# R181A.net
KiCad netlist of a schematic drawn in EAGLE
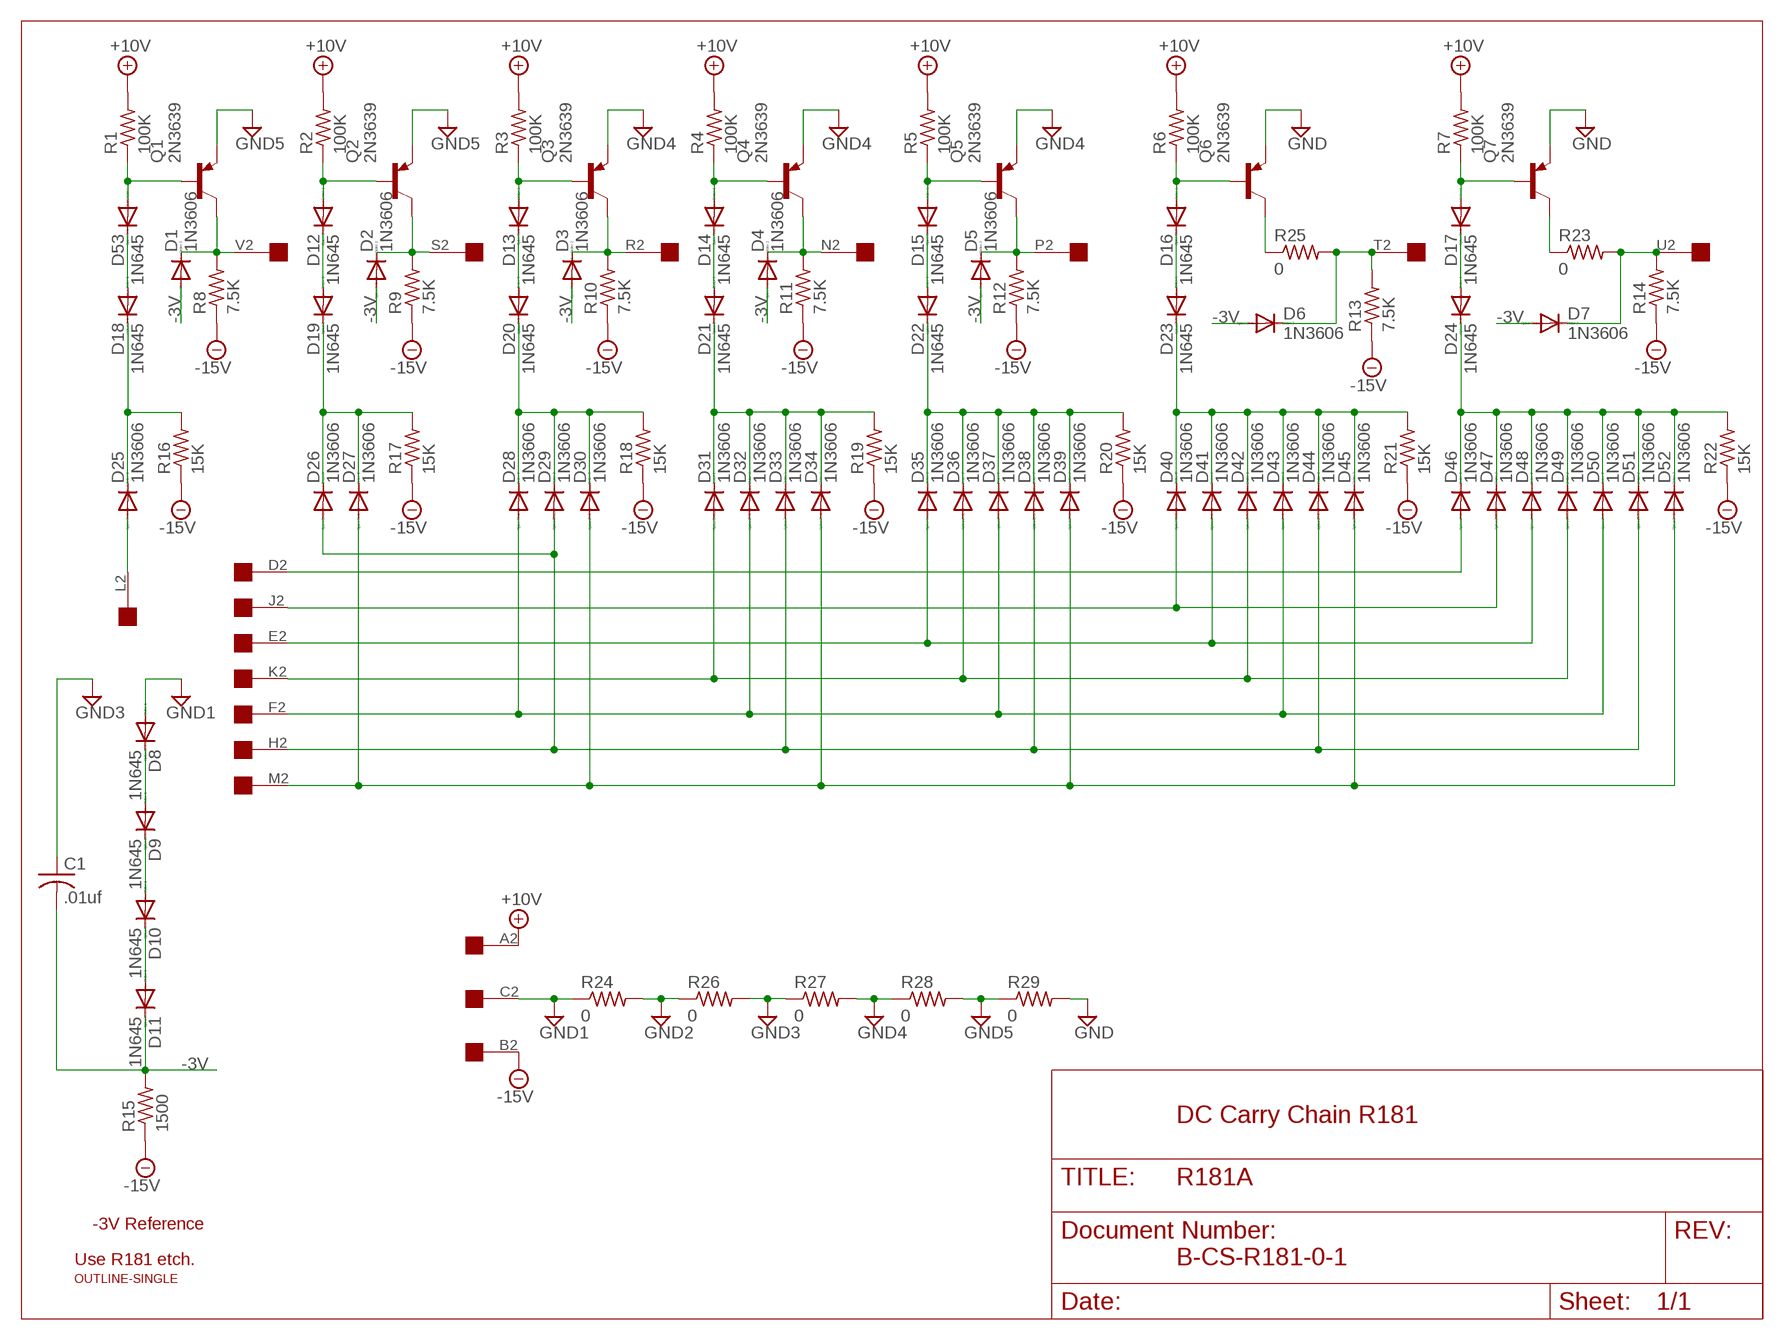
[diagram p0: schematic, sheet 1]

(export (version "E")
  (design (tool "Eeschema 10.0.6"))
  (components
    (comp (ref "C1")
      (value ".01uf")
      (footprint "eagle-import:C050-025X075")
      (libsource (lib "eagle-import") (part "C-US050-025X075"))
    )
    (comp (ref "D1")
      (value "1N3606")
      (footprint "eagle-import:DO35-10")
      (libsource (lib "eagle-import") (part "1N4148DO35-10"))
    )
    (comp (ref "D2")
      (value "1N3606")
      (footprint "eagle-import:DO35-10")
      (libsource (lib "eagle-import") (part "1N4148DO35-10"))
    )
    (comp (ref "D3")
      (value "1N3606")
      (footprint "eagle-import:DO35-10")
      (libsource (lib "eagle-import") (part "1N4148DO35-10"))
    )
    (comp (ref "D4")
      (value "1N3606")
      (footprint "eagle-import:DO35-10")
      (libsource (lib "eagle-import") (part "1N4148DO35-10"))
    )
    (comp (ref "D5")
      (value "1N3606")
      (footprint "eagle-import:DO35-10")
      (libsource (lib "eagle-import") (part "1N4148DO35-10"))
    )
    (comp (ref "D6")
      (value "1N3606")
      (footprint "eagle-import:DO35-10")
      (libsource (lib "eagle-import") (part "1N4148DO35-10"))
    )
    (comp (ref "D7")
      (value "1N3606")
      (footprint "eagle-import:DO35-10")
      (libsource (lib "eagle-import") (part "1N4148DO35-10"))
    )
    (comp (ref "D8")
      (value "1N645")
      (footprint "eagle-import:DO35-10")
      (libsource (lib "eagle-import") (part "1N4148DO35-10"))
    )
    (comp (ref "D9")
      (value "1N645")
      (footprint "eagle-import:DO35-10")
      (libsource (lib "eagle-import") (part "1N4148DO35-10"))
    )
    (comp (ref "D10")
      (value "1N645")
      (footprint "eagle-import:DO35-10")
      (libsource (lib "eagle-import") (part "1N4148DO35-10"))
    )
    (comp (ref "D11")
      (value "1N645")
      (footprint "eagle-import:DO35-10")
      (libsource (lib "eagle-import") (part "1N4148DO35-10"))
    )
    (comp (ref "D12")
      (value "1N645")
      (footprint "eagle-import:DO35-10")
      (libsource (lib "eagle-import") (part "1N4148DO35-10"))
    )
    (comp (ref "D13")
      (value "1N645")
      (footprint "eagle-import:DO35-10")
      (libsource (lib "eagle-import") (part "1N4148DO35-10"))
    )
    (comp (ref "D14")
      (value "1N645")
      (footprint "eagle-import:DO35-10")
      (libsource (lib "eagle-import") (part "1N4148DO35-10"))
    )
    (comp (ref "D15")
      (value "1N645")
      (footprint "eagle-import:DO35-10")
      (libsource (lib "eagle-import") (part "1N4148DO35-10"))
    )
    (comp (ref "D16")
      (value "1N645")
      (footprint "eagle-import:DO35-10")
      (libsource (lib "eagle-import") (part "1N4148DO35-10"))
    )
    (comp (ref "D17")
      (value "1N645")
      (footprint "eagle-import:DO35-10")
      (libsource (lib "eagle-import") (part "1N4148DO35-10"))
    )
    (comp (ref "D18")
      (value "1N645")
      (footprint "eagle-import:DO35-10")
      (libsource (lib "eagle-import") (part "1N4148DO35-10"))
    )
    (comp (ref "D19")
      (value "1N645")
      (footprint "eagle-import:DO35-10")
      (libsource (lib "eagle-import") (part "1N4148DO35-10"))
    )
    (comp (ref "D20")
      (value "1N645")
      (footprint "eagle-import:DO35-10")
      (libsource (lib "eagle-import") (part "1N4148DO35-10"))
    )
    (comp (ref "D21")
      (value "1N645")
      (footprint "eagle-import:DO35-10")
      (libsource (lib "eagle-import") (part "1N4148DO35-10"))
    )
    (comp (ref "D22")
      (value "1N645")
      (footprint "eagle-import:DO35-10")
      (libsource (lib "eagle-import") (part "1N4148DO35-10"))
    )
    (comp (ref "D23")
      (value "1N645")
      (footprint "eagle-import:DO35-10")
      (libsource (lib "eagle-import") (part "1N4148DO35-10"))
    )
    (comp (ref "D24")
      (value "1N645")
      (footprint "eagle-import:DO35-10")
      (libsource (lib "eagle-import") (part "1N4148DO35-10"))
    )
    (comp (ref "D25")
      (value "1N3606")
      (footprint "eagle-import:DO35-10")
      (libsource (lib "eagle-import") (part "1N4148DO35-10"))
    )
    (comp (ref "D26")
      (value "1N3606")
      (footprint "eagle-import:DO35-10")
      (libsource (lib "eagle-import") (part "1N4148DO35-10"))
    )
    (comp (ref "D27")
      (value "1N3606")
      (footprint "eagle-import:DO35-10")
      (libsource (lib "eagle-import") (part "1N4148DO35-10"))
    )
    (comp (ref "D28")
      (value "1N3606")
      (footprint "eagle-import:DO35-10")
      (libsource (lib "eagle-import") (part "1N4148DO35-10"))
    )
    (comp (ref "D29")
      (value "1N3606")
      (footprint "eagle-import:DO35-10")
      (libsource (lib "eagle-import") (part "1N4148DO35-10"))
    )
    (comp (ref "D30")
      (value "1N3606")
      (footprint "eagle-import:DO35-10")
      (libsource (lib "eagle-import") (part "1N4148DO35-10"))
    )
    (comp (ref "D31")
      (value "1N3606")
      (footprint "eagle-import:DO35-10")
      (libsource (lib "eagle-import") (part "1N4148DO35-10"))
    )
    (comp (ref "D32")
      (value "1N3606")
      (footprint "eagle-import:DO35-10")
      (libsource (lib "eagle-import") (part "1N4148DO35-10"))
    )
    (comp (ref "D33")
      (value "1N3606")
      (footprint "eagle-import:DO35-10")
      (libsource (lib "eagle-import") (part "1N4148DO35-10"))
    )
    (comp (ref "D34")
      (value "1N3606")
      (footprint "eagle-import:DO35-10")
      (libsource (lib "eagle-import") (part "1N4148DO35-10"))
    )
    (comp (ref "D35")
      (value "1N3606")
      (footprint "eagle-import:DO35-10")
      (libsource (lib "eagle-import") (part "1N4148DO35-10"))
    )
    (comp (ref "D36")
      (value "1N3606")
      (footprint "eagle-import:DO35-10")
      (libsource (lib "eagle-import") (part "1N4148DO35-10"))
    )
    (comp (ref "D37")
      (value "1N3606")
      (footprint "eagle-import:DO35-10")
      (libsource (lib "eagle-import") (part "1N4148DO35-10"))
    )
    (comp (ref "D38")
      (value "1N3606")
      (footprint "eagle-import:DO35-10")
      (libsource (lib "eagle-import") (part "1N4148DO35-10"))
    )
    (comp (ref "D39")
      (value "1N3606")
      (footprint "eagle-import:DO35-10")
      (libsource (lib "eagle-import") (part "1N4148DO35-10"))
    )
    (comp (ref "D40")
      (value "1N3606")
      (footprint "eagle-import:DO35-10")
      (libsource (lib "eagle-import") (part "1N4148DO35-10"))
    )
    (comp (ref "D41")
      (value "1N3606")
      (footprint "eagle-import:DO35-10")
      (libsource (lib "eagle-import") (part "1N4148DO35-10"))
    )
    (comp (ref "D42")
      (value "1N3606")
      (footprint "eagle-import:DO35-10")
      (libsource (lib "eagle-import") (part "1N4148DO35-10"))
    )
    (comp (ref "D43")
      (value "1N3606")
      (footprint "eagle-import:DO35-10")
      (libsource (lib "eagle-import") (part "1N4148DO35-10"))
    )
    (comp (ref "D44")
      (value "1N3606")
      (footprint "eagle-import:DO35-10")
      (libsource (lib "eagle-import") (part "1N4148DO35-10"))
    )
    (comp (ref "D45")
      (value "1N3606")
      (footprint "eagle-import:DO35-10")
      (libsource (lib "eagle-import") (part "1N4148DO35-10"))
    )
    (comp (ref "D46")
      (value "1N3606")
      (footprint "eagle-import:DO35-10")
      (libsource (lib "eagle-import") (part "1N4148DO35-10"))
    )
    (comp (ref "D47")
      (value "1N3606")
      (footprint "eagle-import:DO35-10")
      (libsource (lib "eagle-import") (part "1N4148DO35-10"))
    )
    (comp (ref "D48")
      (value "1N3606")
      (footprint "eagle-import:DO35-10")
      (libsource (lib "eagle-import") (part "1N4148DO35-10"))
    )
    (comp (ref "D49")
      (value "1N3606")
      (footprint "eagle-import:DO35-10")
      (libsource (lib "eagle-import") (part "1N4148DO35-10"))
    )
    (comp (ref "D50")
      (value "1N3606")
      (footprint "eagle-import:DO35-10")
      (libsource (lib "eagle-import") (part "1N4148DO35-10"))
    )
    (comp (ref "D51")
      (value "1N3606")
      (footprint "eagle-import:DO35-10")
      (libsource (lib "eagle-import") (part "1N4148DO35-10"))
    )
    (comp (ref "D52")
      (value "1N3606")
      (footprint "eagle-import:DO35-10")
      (libsource (lib "eagle-import") (part "1N4148DO35-10"))
    )
    (comp (ref "D53")
      (value "1N645")
      (footprint "eagle-import:DO35-10")
      (libsource (lib "eagle-import") (part "1N4148DO35-10"))
    )
    (comp (ref "Q1")
      (value "2N3639")
      (footprint "eagle-import:TO39")
      (libsource (lib "eagle-import") (part "2N3637"))
    )
    (comp (ref "Q2")
      (value "2N3639")
      (footprint "eagle-import:TO39")
      (libsource (lib "eagle-import") (part "2N3637"))
    )
    (comp (ref "Q3")
      (value "2N3639")
      (footprint "eagle-import:TO39")
      (libsource (lib "eagle-import") (part "2N3637"))
    )
    (comp (ref "Q4")
      (value "2N3639")
      (footprint "eagle-import:TO39")
      (libsource (lib "eagle-import") (part "2N3637"))
    )
    (comp (ref "Q5")
      (value "2N3639")
      (footprint "eagle-import:TO39")
      (libsource (lib "eagle-import") (part "2N3637"))
    )
    (comp (ref "Q6")
      (value "2N3639")
      (footprint "eagle-import:TO39")
      (libsource (lib "eagle-import") (part "2N3637"))
    )
    (comp (ref "Q7")
      (value "2N3639")
      (footprint "eagle-import:TO39")
      (libsource (lib "eagle-import") (part "2N3637"))
    )
    (comp (ref "R1")
      (value "100K")
      (footprint "eagle-import:0207_10")
      (libsource (lib "eagle-import") (part "R-US_0207/10"))
    )
    (comp (ref "R2")
      (value "100K")
      (footprint "eagle-import:0207_10")
      (libsource (lib "eagle-import") (part "R-US_0207/10"))
    )
    (comp (ref "R3")
      (value "100K")
      (footprint "eagle-import:0207_10")
      (libsource (lib "eagle-import") (part "R-US_0207/10"))
    )
    (comp (ref "R4")
      (value "100K")
      (footprint "eagle-import:0207_10")
      (libsource (lib "eagle-import") (part "R-US_0207/10"))
    )
    (comp (ref "R5")
      (value "100K")
      (footprint "eagle-import:0207_10")
      (libsource (lib "eagle-import") (part "R-US_0207/10"))
    )
    (comp (ref "R6")
      (value "100K")
      (footprint "eagle-import:0207_10")
      (libsource (lib "eagle-import") (part "R-US_0207/10"))
    )
    (comp (ref "R7")
      (value "100K")
      (footprint "eagle-import:0207_10")
      (libsource (lib "eagle-import") (part "R-US_0207/10"))
    )
    (comp (ref "R8")
      (value "7.5K")
      (footprint "eagle-import:0207_10")
      (libsource (lib "eagle-import") (part "R-US_0207/10"))
    )
    (comp (ref "R9")
      (value "7.5K")
      (footprint "eagle-import:0207_10")
      (libsource (lib "eagle-import") (part "R-US_0207/10"))
    )
    (comp (ref "R10")
      (value "7.5K")
      (footprint "eagle-import:0207_10")
      (libsource (lib "eagle-import") (part "R-US_0207/10"))
    )
    (comp (ref "R11")
      (value "7.5K")
      (footprint "eagle-import:0207_10")
      (libsource (lib "eagle-import") (part "R-US_0207/10"))
    )
    (comp (ref "R12")
      (value "7.5K")
      (footprint "eagle-import:0207_10")
      (libsource (lib "eagle-import") (part "R-US_0207/10"))
    )
    (comp (ref "R13")
      (value "7.5K")
      (footprint "eagle-import:0207_10")
      (libsource (lib "eagle-import") (part "R-US_0207/10"))
    )
    (comp (ref "R14")
      (value "7.5K")
      (footprint "eagle-import:0207_10")
      (libsource (lib "eagle-import") (part "R-US_0207/10"))
    )
    (comp (ref "R15")
      (value "1500")
      (footprint "eagle-import:0207_10")
      (libsource (lib "eagle-import") (part "R-US_0207/10"))
    )
    (comp (ref "R16")
      (value "15K")
      (footprint "eagle-import:0207_10")
      (libsource (lib "eagle-import") (part "R-US_0207/10"))
    )
    (comp (ref "R17")
      (value "15K")
      (footprint "eagle-import:0207_10")
      (libsource (lib "eagle-import") (part "R-US_0207/10"))
    )
    (comp (ref "R18")
      (value "15K")
      (footprint "eagle-import:0207_10")
      (libsource (lib "eagle-import") (part "R-US_0207/10"))
    )
    (comp (ref "R19")
      (value "15K")
      (footprint "eagle-import:0207_10")
      (libsource (lib "eagle-import") (part "R-US_0207/10"))
    )
    (comp (ref "R20")
      (value "15K")
      (footprint "eagle-import:0207_10")
      (libsource (lib "eagle-import") (part "R-US_0207/10"))
    )
    (comp (ref "R21")
      (value "15K")
      (footprint "eagle-import:0207_10")
      (libsource (lib "eagle-import") (part "R-US_0207/10"))
    )
    (comp (ref "R22")
      (value "15K")
      (footprint "eagle-import:0207_10")
      (libsource (lib "eagle-import") (part "R-US_0207/10"))
    )
    (comp (ref "R23")
      (value "0")
      (footprint "eagle-import:0207_10")
      (libsource (lib "eagle-import") (part "R-US_0207/10"))
    )
    (comp (ref "R24")
      (value "0")
      (footprint "eagle-import:0207_10")
      (libsource (lib "eagle-import") (part "R-US_0207/10"))
    )
    (comp (ref "R25")
      (value "0")
      (footprint "eagle-import:0207_10")
      (libsource (lib "eagle-import") (part "R-US_0207/10"))
    )
    (comp (ref "R26")
      (value "0")
      (footprint "eagle-import:0207_10")
      (libsource (lib "eagle-import") (part "R-US_0207/10"))
    )
    (comp (ref "R27")
      (value "0")
      (footprint "eagle-import:0207_10")
      (libsource (lib "eagle-import") (part "R-US_0207/10"))
    )
    (comp (ref "R28")
      (value "0")
      (footprint "eagle-import:0207_10")
      (libsource (lib "eagle-import") (part "R-US_0207/10"))
    )
    (comp (ref "R29")
      (value "0")
      (footprint "eagle-import:0207_10")
      (libsource (lib "eagle-import") (part "R-US_0207/10"))
    )
    (comp (ref "U$1")
      (value "OUTLINE-SINGLE")
      (footprint "eagle-import:SINGLE")
      (libsource (lib "eagle-import") (part "OUTLINE-SINGLE"))
    )
    (comp (ref "U$2")
      (value "EDGE-1")
      (footprint "eagle-import:EDGE-CON1")
      (libsource (lib "eagle-import") (part "EDGE-1"))
    )
  )
  (nets
    (net (code "1") (name "+10V") (class "Default")
      (node (ref "R1") (pin "2") (pinfunction "2_2") (pintype "passive"))
      (node (ref "R2") (pin "2") (pinfunction "2_2") (pintype "passive"))
      (node (ref "R3") (pin "2") (pinfunction "2_2") (pintype "passive"))
      (node (ref "R4") (pin "2") (pinfunction "2_2") (pintype "passive"))
      (node (ref "R5") (pin "2") (pinfunction "2_2") (pintype "passive"))
      (node (ref "R6") (pin "2") (pinfunction "2_2") (pintype "passive"))
      (node (ref "R7") (pin "2") (pinfunction "2_2") (pintype "passive"))
      (node (ref "U$2") (pin "A2") (pinfunction "1_A2") (pintype "bidirectional"))
    )
    (net (code "2") (name "-15V") (class "Default")
      (node (ref "R10") (pin "1") (pinfunction "1_1") (pintype "passive"))
      (node (ref "R11") (pin "1") (pinfunction "1_1") (pintype "passive"))
      (node (ref "R12") (pin "1") (pinfunction "1_1") (pintype "passive"))
      (node (ref "R13") (pin "1") (pinfunction "1_1") (pintype "passive"))
      (node (ref "R14") (pin "1") (pinfunction "1_1") (pintype "passive"))
      (node (ref "R15") (pin "1") (pinfunction "1_1") (pintype "passive"))
      (node (ref "R16") (pin "1") (pinfunction "1_1") (pintype "passive"))
      (node (ref "R17") (pin "1") (pinfunction "1_1") (pintype "passive"))
      (node (ref "R18") (pin "1") (pinfunction "1_1") (pintype "passive"))
      (node (ref "R19") (pin "1") (pinfunction "1_1") (pintype "passive"))
      (node (ref "R20") (pin "1") (pinfunction "1_1") (pintype "passive"))
      (node (ref "R21") (pin "1") (pinfunction "1_1") (pintype "passive"))
      (node (ref "R22") (pin "1") (pinfunction "1_1") (pintype "passive"))
      (node (ref "R8") (pin "1") (pinfunction "1_1") (pintype "passive"))
      (node (ref "R9") (pin "1") (pinfunction "1_1") (pintype "passive"))
      (node (ref "U$2") (pin "B2") (pinfunction "1_B2") (pintype "bidirectional"))
    )
    (net (code "3") (name "/-3V") (class "Default")
      (node (ref "C1") (pin "2") (pinfunction "2_2") (pintype "passive"))
      (node (ref "D1") (pin "A") (pinfunction "A_A") (pintype "passive"))
      (node (ref "D11") (pin "C") (pinfunction "C_C") (pintype "passive"))
      (node (ref "D2") (pin "A") (pinfunction "A_A") (pintype "passive"))
      (node (ref "D3") (pin "A") (pinfunction "A_A") (pintype "passive"))
      (node (ref "D4") (pin "A") (pinfunction "A_A") (pintype "passive"))
      (node (ref "D5") (pin "A") (pinfunction "A_A") (pintype "passive"))
      (node (ref "D6") (pin "A") (pinfunction "A_A") (pintype "passive"))
      (node (ref "D7") (pin "A") (pinfunction "A_A") (pintype "passive"))
      (node (ref "R15") (pin "2") (pinfunction "2_2") (pintype "passive"))
    )
    (net (code "4") (name "GND") (class "Default")
      (node (ref "Q6") (pin "1") (pinfunction "E_1") (pintype "passive"))
      (node (ref "Q7") (pin "1") (pinfunction "E_1") (pintype "passive"))
      (node (ref "R29") (pin "2") (pinfunction "2_2") (pintype "passive"))
    )
    (net (code "5") (name "GND1") (class "Default")
      (node (ref "D8") (pin "A") (pinfunction "A_A") (pintype "passive"))
      (node (ref "R24") (pin "1") (pinfunction "1_1") (pintype "passive"))
      (node (ref "U$2") (pin "C2") (pinfunction "1_C2") (pintype "bidirectional"))
    )
    (net (code "6") (name "GND2") (class "Default")
      (node (ref "R24") (pin "2") (pinfunction "2_2") (pintype "passive"))
      (node (ref "R26") (pin "1") (pinfunction "1_1") (pintype "passive"))
    )
    (net (code "7") (name "GND3") (class "Default")
      (node (ref "C1") (pin "1") (pinfunction "1_1") (pintype "passive"))
      (node (ref "R26") (pin "2") (pinfunction "2_2") (pintype "passive"))
      (node (ref "R27") (pin "1") (pinfunction "1_1") (pintype "passive"))
    )
    (net (code "8") (name "GND4") (class "Default")
      (node (ref "Q3") (pin "1") (pinfunction "E_1") (pintype "passive"))
      (node (ref "Q4") (pin "1") (pinfunction "E_1") (pintype "passive"))
      (node (ref "Q5") (pin "1") (pinfunction "E_1") (pintype "passive"))
      (node (ref "R27") (pin "2") (pinfunction "2_2") (pintype "passive"))
      (node (ref "R28") (pin "1") (pinfunction "1_1") (pintype "passive"))
    )
    (net (code "9") (name "GND5") (class "Default")
      (node (ref "Q1") (pin "1") (pinfunction "E_1") (pintype "passive"))
      (node (ref "Q2") (pin "1") (pinfunction "E_1") (pintype "passive"))
      (node (ref "R28") (pin "2") (pinfunction "2_2") (pintype "passive"))
      (node (ref "R29") (pin "1") (pinfunction "1_1") (pintype "passive"))
    )
    (net (code "10") (name "Net-(D8-PadC)") (class "Default")
      (node (ref "D8") (pin "C") (pinfunction "C_C") (pintype "passive"))
      (node (ref "D9") (pin "A") (pinfunction "A_A") (pintype "passive"))
    )
    (net (code "11") (name "Net-(D10-PadA)") (class "Default")
      (node (ref "D10") (pin "A") (pinfunction "A_A") (pintype "passive"))
      (node (ref "D9") (pin "C") (pinfunction "C_C") (pintype "passive"))
    )
    (net (code "12") (name "Net-(D10-PadC)") (class "Default")
      (node (ref "D10") (pin "C") (pinfunction "C_C") (pintype "passive"))
      (node (ref "D11") (pin "A") (pinfunction "A_A") (pintype "passive"))
    )
    (net (code "13") (name "Net-(D12-PadC)") (class "Default")
      (node (ref "D12") (pin "C") (pinfunction "C_C") (pintype "passive"))
      (node (ref "D19") (pin "A") (pinfunction "A_A") (pintype "passive"))
    )
    (net (code "14") (name "Net-(D13-PadC)") (class "Default")
      (node (ref "D13") (pin "C") (pinfunction "C_C") (pintype "passive"))
      (node (ref "D20") (pin "A") (pinfunction "A_A") (pintype "passive"))
    )
    (net (code "15") (name "Net-(D14-PadC)") (class "Default")
      (node (ref "D14") (pin "C") (pinfunction "C_C") (pintype "passive"))
      (node (ref "D21") (pin "A") (pinfunction "A_A") (pintype "passive"))
    )
    (net (code "16") (name "Net-(D15-PadC)") (class "Default")
      (node (ref "D15") (pin "C") (pinfunction "C_C") (pintype "passive"))
      (node (ref "D22") (pin "A") (pinfunction "A_A") (pintype "passive"))
    )
    (net (code "17") (name "Net-(D16-PadC)") (class "Default")
      (node (ref "D16") (pin "C") (pinfunction "C_C") (pintype "passive"))
      (node (ref "D23") (pin "A") (pinfunction "A_A") (pintype "passive"))
    )
    (net (code "18") (name "Net-(D17-PadC)") (class "Default")
      (node (ref "D17") (pin "C") (pinfunction "C_C") (pintype "passive"))
      (node (ref "D24") (pin "A") (pinfunction "A_A") (pintype "passive"))
    )
    (net (code "19") (name "Net-(D18-PadA)") (class "Default")
      (node (ref "D18") (pin "A") (pinfunction "A_A") (pintype "passive"))
      (node (ref "D53") (pin "C") (pinfunction "C_C") (pintype "passive"))
    )
    (net (code "20") (name "Net-(D18-PadC)") (class "Default")
      (node (ref "D18") (pin "C") (pinfunction "C_C") (pintype "passive"))
      (node (ref "D25") (pin "C") (pinfunction "C_C") (pintype "passive"))
      (node (ref "R16") (pin "2") (pinfunction "2_2") (pintype "passive"))
    )
    (net (code "21") (name "Net-(D19-PadC)") (class "Default")
      (node (ref "D19") (pin "C") (pinfunction "C_C") (pintype "passive"))
      (node (ref "D26") (pin "C") (pinfunction "C_C") (pintype "passive"))
      (node (ref "D27") (pin "C") (pinfunction "C_C") (pintype "passive"))
      (node (ref "R17") (pin "2") (pinfunction "2_2") (pintype "passive"))
    )
    (net (code "22") (name "Net-(D20-PadC)") (class "Default")
      (node (ref "D20") (pin "C") (pinfunction "C_C") (pintype "passive"))
      (node (ref "D28") (pin "C") (pinfunction "C_C") (pintype "passive"))
      (node (ref "D29") (pin "C") (pinfunction "C_C") (pintype "passive"))
      (node (ref "D30") (pin "C") (pinfunction "C_C") (pintype "passive"))
      (node (ref "R18") (pin "2") (pinfunction "2_2") (pintype "passive"))
    )
    (net (code "23") (name "Net-(D21-PadC)") (class "Default")
      (node (ref "D21") (pin "C") (pinfunction "C_C") (pintype "passive"))
      (node (ref "D31") (pin "C") (pinfunction "C_C") (pintype "passive"))
      (node (ref "D32") (pin "C") (pinfunction "C_C") (pintype "passive"))
      (node (ref "D33") (pin "C") (pinfunction "C_C") (pintype "passive"))
      (node (ref "D34") (pin "C") (pinfunction "C_C") (pintype "passive"))
      (node (ref "R19") (pin "2") (pinfunction "2_2") (pintype "passive"))
    )
    (net (code "24") (name "Net-(D22-PadC)") (class "Default")
      (node (ref "D22") (pin "C") (pinfunction "C_C") (pintype "passive"))
      (node (ref "D35") (pin "C") (pinfunction "C_C") (pintype "passive"))
      (node (ref "D36") (pin "C") (pinfunction "C_C") (pintype "passive"))
      (node (ref "D37") (pin "C") (pinfunction "C_C") (pintype "passive"))
      (node (ref "D38") (pin "C") (pinfunction "C_C") (pintype "passive"))
      (node (ref "D39") (pin "C") (pinfunction "C_C") (pintype "passive"))
      (node (ref "R20") (pin "2") (pinfunction "2_2") (pintype "passive"))
    )
    (net (code "25") (name "Net-(D23-PadC)") (class "Default")
      (node (ref "D23") (pin "C") (pinfunction "C_C") (pintype "passive"))
      (node (ref "D40") (pin "C") (pinfunction "C_C") (pintype "passive"))
      (node (ref "D41") (pin "C") (pinfunction "C_C") (pintype "passive"))
      (node (ref "D42") (pin "C") (pinfunction "C_C") (pintype "passive"))
      (node (ref "D43") (pin "C") (pinfunction "C_C") (pintype "passive"))
      (node (ref "D44") (pin "C") (pinfunction "C_C") (pintype "passive"))
      (node (ref "D45") (pin "C") (pinfunction "C_C") (pintype "passive"))
      (node (ref "R21") (pin "2") (pinfunction "2_2") (pintype "passive"))
    )
    (net (code "26") (name "Net-(D24-PadC)") (class "Default")
      (node (ref "D24") (pin "C") (pinfunction "C_C") (pintype "passive"))
      (node (ref "D46") (pin "C") (pinfunction "C_C") (pintype "passive"))
      (node (ref "D47") (pin "C") (pinfunction "C_C") (pintype "passive"))
      (node (ref "D48") (pin "C") (pinfunction "C_C") (pintype "passive"))
      (node (ref "D49") (pin "C") (pinfunction "C_C") (pintype "passive"))
      (node (ref "D50") (pin "C") (pinfunction "C_C") (pintype "passive"))
      (node (ref "D51") (pin "C") (pinfunction "C_C") (pintype "passive"))
      (node (ref "D52") (pin "C") (pinfunction "C_C") (pintype "passive"))
      (node (ref "R22") (pin "2") (pinfunction "2_2") (pintype "passive"))
    )
    (net (code "27") (name "Net-(Q1-B)") (class "Default")
      (node (ref "D53") (pin "A") (pinfunction "A_A") (pintype "passive"))
      (node (ref "Q1") (pin "2") (pinfunction "B_2") (pintype "passive"))
      (node (ref "R1") (pin "1") (pinfunction "1_1") (pintype "passive"))
    )
    (net (code "28") (name "Net-(Q1-C)") (class "Default")
      (node (ref "D1") (pin "C") (pinfunction "C_C") (pintype "passive"))
      (node (ref "Q1") (pin "3") (pinfunction "C_3") (pintype "passive"))
      (node (ref "R8") (pin "2") (pinfunction "2_2") (pintype "passive"))
      (node (ref "U$2") (pin "V2") (pinfunction "1_V2") (pintype "bidirectional"))
    )
    (net (code "29") (name "Net-(Q2-B)") (class "Default")
      (node (ref "D12") (pin "A") (pinfunction "A_A") (pintype "passive"))
      (node (ref "Q2") (pin "2") (pinfunction "B_2") (pintype "passive"))
      (node (ref "R2") (pin "1") (pinfunction "1_1") (pintype "passive"))
    )
    (net (code "30") (name "Net-(Q2-C)") (class "Default")
      (node (ref "D2") (pin "C") (pinfunction "C_C") (pintype "passive"))
      (node (ref "Q2") (pin "3") (pinfunction "C_3") (pintype "passive"))
      (node (ref "R9") (pin "2") (pinfunction "2_2") (pintype "passive"))
      (node (ref "U$2") (pin "S2") (pinfunction "1_S2") (pintype "bidirectional"))
    )
    (net (code "31") (name "Net-(Q3-B)") (class "Default")
      (node (ref "D13") (pin "A") (pinfunction "A_A") (pintype "passive"))
      (node (ref "Q3") (pin "2") (pinfunction "B_2") (pintype "passive"))
      (node (ref "R3") (pin "1") (pinfunction "1_1") (pintype "passive"))
    )
    (net (code "32") (name "Net-(Q3-C)") (class "Default")
      (node (ref "D3") (pin "C") (pinfunction "C_C") (pintype "passive"))
      (node (ref "Q3") (pin "3") (pinfunction "C_3") (pintype "passive"))
      (node (ref "R10") (pin "2") (pinfunction "2_2") (pintype "passive"))
      (node (ref "U$2") (pin "R2") (pinfunction "1_R2") (pintype "bidirectional"))
    )
    (net (code "33") (name "Net-(Q4-B)") (class "Default")
      (node (ref "D14") (pin "A") (pinfunction "A_A") (pintype "passive"))
      (node (ref "Q4") (pin "2") (pinfunction "B_2") (pintype "passive"))
      (node (ref "R4") (pin "1") (pinfunction "1_1") (pintype "passive"))
    )
    (net (code "34") (name "Net-(Q4-C)") (class "Default")
      (node (ref "D4") (pin "C") (pinfunction "C_C") (pintype "passive"))
      (node (ref "Q4") (pin "3") (pinfunction "C_3") (pintype "passive"))
      (node (ref "R11") (pin "2") (pinfunction "2_2") (pintype "passive"))
      (node (ref "U$2") (pin "N2") (pinfunction "1_N2") (pintype "bidirectional"))
    )
    (net (code "35") (name "Net-(Q5-B)") (class "Default")
      (node (ref "D15") (pin "A") (pinfunction "A_A") (pintype "passive"))
      (node (ref "Q5") (pin "2") (pinfunction "B_2") (pintype "passive"))
      (node (ref "R5") (pin "1") (pinfunction "1_1") (pintype "passive"))
    )
    (net (code "36") (name "Net-(Q5-C)") (class "Default")
      (node (ref "D5") (pin "C") (pinfunction "C_C") (pintype "passive"))
      (node (ref "Q5") (pin "3") (pinfunction "C_3") (pintype "passive"))
      (node (ref "R12") (pin "2") (pinfunction "2_2") (pintype "passive"))
      (node (ref "U$2") (pin "P2") (pinfunction "1_P2") (pintype "bidirectional"))
    )
    (net (code "37") (name "Net-(Q6-B)") (class "Default")
      (node (ref "D16") (pin "A") (pinfunction "A_A") (pintype "passive"))
      (node (ref "Q6") (pin "2") (pinfunction "B_2") (pintype "passive"))
      (node (ref "R6") (pin "1") (pinfunction "1_1") (pintype "passive"))
    )
    (net (code "38") (name "Net-(Q6-C)") (class "Default")
      (node (ref "Q6") (pin "3") (pinfunction "C_3") (pintype "passive"))
      (node (ref "R25") (pin "1") (pinfunction "1_1") (pintype "passive"))
    )
    (net (code "39") (name "Net-(Q7-B)") (class "Default")
      (node (ref "D17") (pin "A") (pinfunction "A_A") (pintype "passive"))
      (node (ref "Q7") (pin "2") (pinfunction "B_2") (pintype "passive"))
      (node (ref "R7") (pin "1") (pinfunction "1_1") (pintype "passive"))
    )
    (net (code "40") (name "Net-(Q7-C)") (class "Default")
      (node (ref "Q7") (pin "3") (pinfunction "C_3") (pintype "passive"))
      (node (ref "R23") (pin "1") (pinfunction "1_1") (pintype "passive"))
    )
    (net (code "41") (name "Net-(U$2D-1)") (class "Default")
      (node (ref "D46") (pin "A") (pinfunction "A_A") (pintype "passive"))
      (node (ref "U$2") (pin "D2") (pinfunction "1_D2") (pintype "bidirectional"))
    )
    (net (code "42") (name "Net-(U$2E-1)") (class "Default")
      (node (ref "D35") (pin "A") (pinfunction "A_A") (pintype "passive"))
      (node (ref "D41") (pin "A") (pinfunction "A_A") (pintype "passive"))
      (node (ref "D48") (pin "A") (pinfunction "A_A") (pintype "passive"))
      (node (ref "U$2") (pin "E2") (pinfunction "1_E2") (pintype "bidirectional"))
    )
    (net (code "43") (name "Net-(U$2F-1)") (class "Default")
      (node (ref "D28") (pin "A") (pinfunction "A_A") (pintype "passive"))
      (node (ref "D32") (pin "A") (pinfunction "A_A") (pintype "passive"))
      (node (ref "D37") (pin "A") (pinfunction "A_A") (pintype "passive"))
      (node (ref "D43") (pin "A") (pinfunction "A_A") (pintype "passive"))
      (node (ref "D50") (pin "A") (pinfunction "A_A") (pintype "passive"))
      (node (ref "U$2") (pin "F2") (pinfunction "1_F2") (pintype "bidirectional"))
    )
    (net (code "44") (name "Net-(U$2G-1)") (class "Default")
      (node (ref "D26") (pin "A") (pinfunction "A_A") (pintype "passive"))
      (node (ref "D29") (pin "A") (pinfunction "A_A") (pintype "passive"))
      (node (ref "D33") (pin "A") (pinfunction "A_A") (pintype "passive"))
      (node (ref "D38") (pin "A") (pinfunction "A_A") (pintype "passive"))
      (node (ref "D44") (pin "A") (pinfunction "A_A") (pintype "passive"))
      (node (ref "D51") (pin "A") (pinfunction "A_A") (pintype "passive"))
      (node (ref "U$2") (pin "H2") (pinfunction "1_H2") (pintype "bidirectional"))
    )
    (net (code "45") (name "Net-(U$2H-1)") (class "Default")
      (node (ref "D40") (pin "A") (pinfunction "A_A") (pintype "passive"))
      (node (ref "D47") (pin "A") (pinfunction "A_A") (pintype "passive"))
      (node (ref "U$2") (pin "J2") (pinfunction "1_J2") (pintype "bidirectional"))
    )
    (net (code "46") (name "Net-(U$2I-1)") (class "Default")
      (node (ref "D31") (pin "A") (pinfunction "A_A") (pintype "passive"))
      (node (ref "D36") (pin "A") (pinfunction "A_A") (pintype "passive"))
      (node (ref "D42") (pin "A") (pinfunction "A_A") (pintype "passive"))
      (node (ref "D49") (pin "A") (pinfunction "A_A") (pintype "passive"))
      (node (ref "U$2") (pin "K2") (pinfunction "1_K2") (pintype "bidirectional"))
    )
    (net (code "47") (name "Net-(U$2J-1)") (class "Default")
      (node (ref "D25") (pin "A") (pinfunction "A_A") (pintype "passive"))
      (node (ref "U$2") (pin "L2") (pinfunction "1_L2") (pintype "bidirectional"))
    )
    (net (code "48") (name "Net-(U$2K-1)") (class "Default")
      (node (ref "D27") (pin "A") (pinfunction "A_A") (pintype "passive"))
      (node (ref "D30") (pin "A") (pinfunction "A_A") (pintype "passive"))
      (node (ref "D34") (pin "A") (pinfunction "A_A") (pintype "passive"))
      (node (ref "D39") (pin "A") (pinfunction "A_A") (pintype "passive"))
      (node (ref "D45") (pin "A") (pinfunction "A_A") (pintype "passive"))
      (node (ref "D52") (pin "A") (pinfunction "A_A") (pintype "passive"))
      (node (ref "U$2") (pin "M2") (pinfunction "1_M2") (pintype "bidirectional"))
    )
    (net (code "49") (name "Net-(U$2P-1)") (class "Default")
      (node (ref "D6") (pin "C") (pinfunction "C_C") (pintype "passive"))
      (node (ref "R13") (pin "2") (pinfunction "2_2") (pintype "passive"))
      (node (ref "R25") (pin "2") (pinfunction "2_2") (pintype "passive"))
      (node (ref "U$2") (pin "T2") (pinfunction "1_T2") (pintype "bidirectional"))
    )
    (net (code "50") (name "Net-(U$2Q-1)") (class "Default")
      (node (ref "D7") (pin "C") (pinfunction "C_C") (pintype "passive"))
      (node (ref "R14") (pin "2") (pinfunction "2_2") (pintype "passive"))
      (node (ref "R23") (pin "2") (pinfunction "2_2") (pintype "passive"))
      (node (ref "U$2") (pin "U2") (pinfunction "1_U2") (pintype "bidirectional"))
    )
  )
)
